# Power_Distribution_-_Spares_8-9_5V.net
KiCad netlist of a schematic drawn in Altium Designer
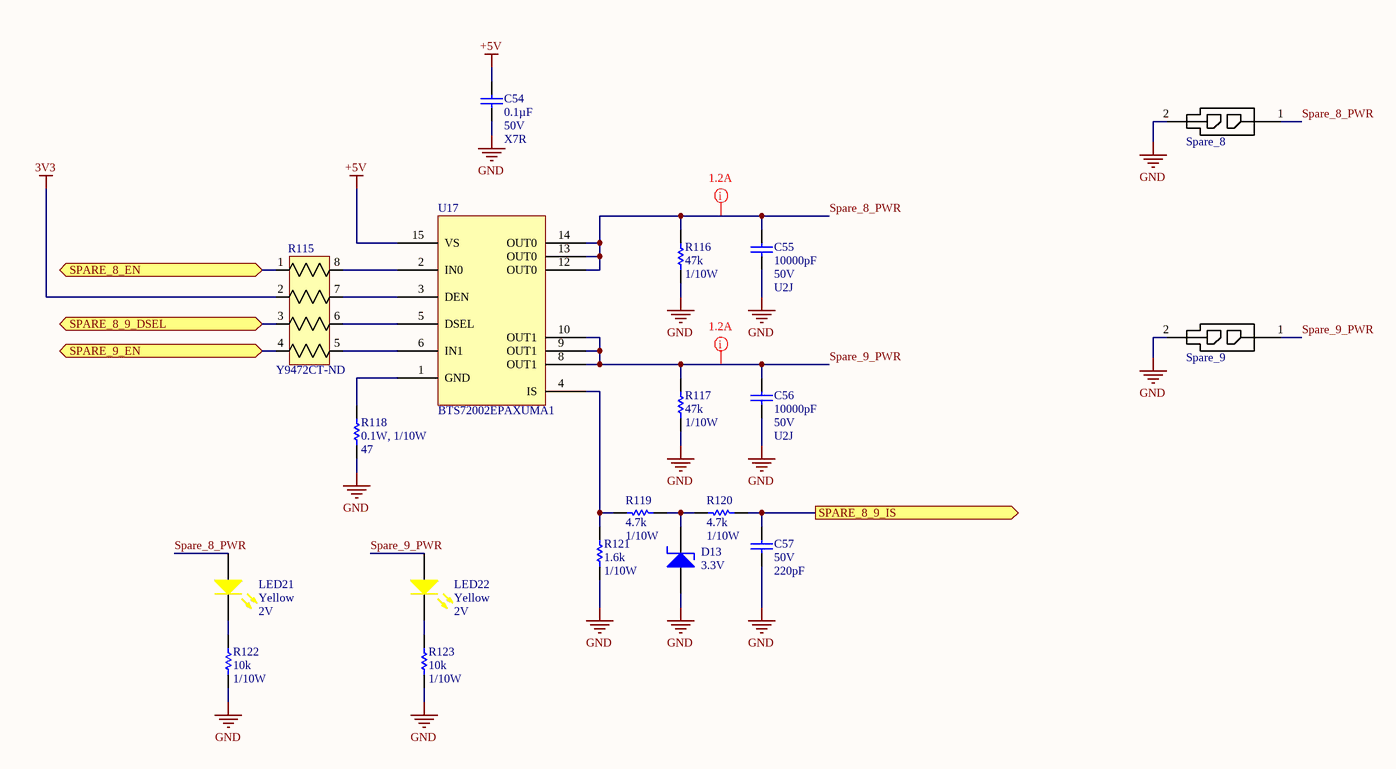
[diagram p0: Power Distribution - Spares 8-9 5V.SchDoc]

(export (version "E")
  (design (tool "Eeschema 10.0.6"))
  (components
    (comp (ref "C54")
      (value "CAP CER 0.1UF 50V 10% X7R 0603")
      (footprint "CAP, 0603")
      (description "0.10µF ±10% 50V Ceramic Capacitor X7R 0603 (1608 Metric)")
      (fields
        (field (name "TOLERANCE") "±10%")
        (field (name "CAPACITANCE") "0.1µF")
        (field (name "VOLTAGE") "50V")
        (field (name "TEMPERATURE COEFFICIENT") "X7R")
      )
      (libsource (lib "Schematic Diagrams") (part "CAP CER 0.1UF 50V 10% X7R 0603"))
    )
    (comp (ref "C55")
      (value "CAP CER 10nF 50V 5% X7R 0603")
      (footprint "CAP, 0603")
      (description "10000pF ±5% 50V Ceramic Capacitor U2J 0603 (1608 Metric)")
      (fields
        (field (name "TOLERANCE") "±5%")
        (field (name "CAPACITANCE") "10000pF")
        (field (name "VOLTAGE") "50V")
        (field (name "TEMPERATURE COEFFICIENT") "U2J")
      )
      (libsource (lib "Schematic Diagrams") (part "CAP CER 10nF 50V 5% X7R 0603"))
    )
    (comp (ref "C56")
      (value "CAP CER 10nF 50V 5% X7R 0603")
      (footprint "CAP, 0603")
      (description "10000pF ±5% 50V Ceramic Capacitor U2J 0603 (1608 Metric)")
      (fields
        (field (name "TOLERANCE") "±5%")
        (field (name "CAPACITANCE") "10000pF")
        (field (name "VOLTAGE") "50V")
        (field (name "TEMPERATURE COEFFICIENT") "U2J")
      )
      (libsource (lib "Schematic Diagrams") (part "CAP CER 10nF 50V 5% X7R 0603"))
    )
    (comp (ref "C57")
      (value "CAP CER 220PF 50V C0G/NP0 0603")
      (footprint "CAP, 0603")
      (description "220pF ±5% 50V Ceramic Capacitor C0G, NP0 0603 (1608 Metric)")
      (fields
        (field (name "MANUFACTURER") "KEMET")
        (field (name "TOLERANCE") "5%")
        (field (name "VOLTAGE RATING") "50V")
        (field (name "CAPACITANCE") "220pF")
      )
      (libsource (lib "Schematic Diagrams") (part "CAP CER 220PF 50V C0G/NP0 0603"))
    )
    (comp (ref "D13")
      (value "DIODE ZENER 3.3V 200MW SOD323")
      (footprint "sod-323")
      (description "Zener Diode 3.3V 200mW ±5% Surface Mount SOD-323")
      (fields (field (name "VOLTAGE") "3.3V"))
      (libsource (lib "Schematic Diagrams") (part "DIODE ZENER 3.3V 200MW SOD323"))
    )
    (comp (ref "LED21")
      (value "LED YELLOW CLEAR 2.1V 0603")
      (footprint "LED_0603")
      (description "Yellow 590nm LED Indication - Discrete 2V 0603 (1608 Metric)")
      (fields
        (field (name "MANUFACTURER") "Wurth Electronics Inc.")
        (field (name "MANUFACTURER PART NUMBER") "150060YS75000")
        (field (name "COLOR") "Yellow")
        (field (name "VOLTAGE - FORWARD (VF) (TYP)") "2V")
      )
      (libsource (lib "Schematic Diagrams") (part "LED YELLOW CLEAR 2.1V 0603"))
    )
    (comp (ref "LED22")
      (value "LED YELLOW CLEAR 2.1V 0603")
      (footprint "LED_0603")
      (description "Yellow 590nm LED Indication - Discrete 2V 0603 (1608 Metric)")
      (fields
        (field (name "MANUFACTURER") "Wurth Electronics Inc.")
        (field (name "MANUFACTURER PART NUMBER") "150060YS75000")
        (field (name "COLOR") "Yellow")
        (field (name "VOLTAGE - FORWARD (VF) (TYP)") "2V")
      )
      (libsource (lib "Schematic Diagrams") (part "LED YELLOW CLEAR 2.1V 0603"))
    )
    (comp (ref "R115")
      (value "RES ARRAY 4 RES 4.7K OHM 1206")
      (footprint "RES ARRAY 4RES 1206")
      (fields (field (name "TOLERANCE") "±5%") (field (name "SUPPLIER PART NUMBER 1") "Y9472CT-ND"))
      (libsource (lib "Schematic Diagrams") (part "RES ARRAY 4 RES 4.7K OHM 1206"))
    )
    (comp (ref "R116")
      (value "RES 47K OHM 1% 1/10W 0603")
      (footprint "RES, 0603")
      (description "47 kOhms ±1% 0.1W, 1/10W Chip Resistor 0603 (1608 Metric) Automotive AEC-Q200 Thick Film")
      (fields
        (field (name "MANUFACTURER") "Panasonic")
        (field (name "MANUFACTURER PART NUMBER") "ERJ3EKF4702V")
        (field (name "RESISTANCE") "47k")
        (field (name "POWER RATING") "1/10W")
      )
      (libsource (lib "Schematic Diagrams") (part "RES 47K OHM 1% 1/10W 0603"))
    )
    (comp (ref "R117")
      (value "RES 47K OHM 1% 1/10W 0603")
      (footprint "RES, 0603")
      (description "47 kOhms ±1% 0.1W, 1/10W Chip Resistor 0603 (1608 Metric) Automotive AEC-Q200 Thick Film")
      (fields
        (field (name "MANUFACTURER") "Panasonic")
        (field (name "MANUFACTURER PART NUMBER") "ERJ3EKF4702V")
        (field (name "RESISTANCE") "47k")
        (field (name "POWER RATING") "1/10W")
      )
      (libsource (lib "Schematic Diagrams") (part "RES 47K OHM 1% 1/10W 0603"))
    )
    (comp (ref "R118")
      (value "RES SMD 47 OHM 1% 1/10W 0603")
      (footprint "RES, 0603")
      (fields
        (field (name "TOLERANCE") "±1%")
        (field (name "POWER (WATTS)") "0.1W, 1/10W")
        (field (name "VALUES") "47")
      )
      (libsource (lib "Schematic Diagrams") (part "RES SMD 47 OHM 1% 1/10W 0603"))
    )
    (comp (ref "R119")
      (value "RES 4.7K OHM 1% 1/10W 0603")
      (footprint "RES, 0603")
      (description "4.7k Ohm ±1% 0.1W, 1/10W Chip Resistor 0603 (1608 Metric) Moisture Resistant Thick Film")
      (fields
        (field (name "TOLERANCE") "±1%")
        (field (name "RESISTANCE (OHMS)") "4.7k")
        (field (name "POWER (WATTS)") "1/10W")
      )
      (libsource (lib "Schematic Diagrams") (part "RES 4.7K OHM 1% 1/10W 0603"))
    )
    (comp (ref "R120")
      (value "RES 4.7K OHM 1% 1/10W 0603")
      (footprint "RES, 0603")
      (description "4.7k Ohm ±1% 0.1W, 1/10W Chip Resistor 0603 (1608 Metric) Moisture Resistant Thick Film")
      (fields
        (field (name "TOLERANCE") "±1%")
        (field (name "RESISTANCE (OHMS)") "4.7k")
        (field (name "POWER (WATTS)") "1/10W")
      )
      (libsource (lib "Schematic Diagrams") (part "RES 4.7K OHM 1% 1/10W 0603"))
    )
    (comp (ref "R121")
      (value "RES 1.6K OHM 1% 1/10W 0603")
      (footprint "RES, 0603")
      (description "1.6 kOhms ±1% 0.1W, 1/10W Chip Resistor 0603 (1608 Metric) Moisture Resistant Thick Film")
      (fields
        (field (name "MANUFACTURER") "Yageo")
        (field (name "MANUFACTURER PART NUMBER") "RC0603FR-071K6L")
        (field (name "RESISTANCE") "1.6k")
        (field (name "POWER RATING") "1/10W")
      )
      (libsource (lib "Schematic Diagrams") (part "RES 1.6K OHM 1% 1/10W 0603"))
    )
    (comp (ref "R122")
      (value "RES 10K OHM 1% 1/10W 0603")
      (footprint "RES, 0603")
      (description "RES SMD 10K OHM 1% 1/10W 0603")
      (fields
        (field (name "TOLERANCE") "±1%")
        (field (name "RESISTANCE") "10k")
        (field (name "POWER") "1/10W")
      )
      (libsource (lib "Schematic Diagrams") (part "RES 10K OHM 1% 1/10W 0603"))
    )
    (comp (ref "R123")
      (value "RES 10K OHM 1% 1/10W 0603")
      (footprint "RES, 0603")
      (description "RES SMD 10K OHM 1% 1/10W 0603")
      (fields
        (field (name "TOLERANCE") "±1%")
        (field (name "RESISTANCE") "10k")
        (field (name "POWER") "1/10W")
      )
      (libsource (lib "Schematic Diagrams") (part "RES 10K OHM 1% 1/10W 0603"))
    )
    (comp (ref "Spare_8")
      (value "CONN 2POS MICRO-FIT 3mm")
      (footprint "CONN, 2POS MICRO-FIT")
      (description "Connector Header Through Hole 2 position")
      (fields (field (name "MANUFACTURER") "Molex") (field (name "MANUFACTURER PART NUMBER") "43045-0227"))
      (libsource (lib "Schematic Diagrams") (part "CONN 2POS MICRO-FIT 3mm"))
    )
    (comp (ref "Spare_9")
      (value "CONN 2POS MICRO-FIT 3mm")
      (footprint "CONN, 2POS MICRO-FIT")
      (description "Connector Header Through Hole 2 position")
      (fields (field (name "MANUFACTURER") "Molex") (field (name "MANUFACTURER PART NUMBER") "43045-0227"))
      (libsource (lib "Schematic Diagrams") (part "CONN 2POS MICRO-FIT 3mm"))
    )
    (comp (ref "U17")
      (value "IC LOAD SWITCH BTS7200-2EPA PG-TSDSO-14_1")
      (footprint "IC LOAD SWITCH PG-TSDSO-14-22")
      (description "Power Switch/Driver 1:1 N-Channel 1.2A PG-TSDSO-14-22")
      (fields
        (field (name "MANUFACTURER") "Infineon")
        (field (name "MANUFACTURER PART NUMBER") "BTS72002EPAXUMA1")
      )
      (libsource (lib "Schematic Diagrams") (part "IC LOAD SWITCH BTS7200-2EPA PG-TSDSO-14_1"))
    )
  )
  (nets
    (net (code "1") (name "+5V") (class "Default")
      (node (ref "C54") (pin "1") (pinfunction "1_1") (pintype "passive"))
      (node (ref "U17") (pin "15") (pinfunction "VS_15") (pintype "passive"))
    )
    (net (code "2") (name "/SPARE_8_9_DSEL") (class "Default")
      (node (ref "R115") (pin "3") (pinfunction "3_3") (pintype "passive"))
    )
    (net (code "3") (name "/SPARE_8_9_IS") (class "Default")
      (node (ref "C57") (pin "1") (pinfunction "1_1") (pintype "passive"))
      (node (ref "R120") (pin "1") (pinfunction "1_1") (pintype "passive"))
    )
    (net (code "4") (name "/SPARE_8_EN") (class "Default")
      (node (ref "R115") (pin "1") (pinfunction "1_1") (pintype "passive"))
    )
    (net (code "5") (name "/SPARE_9_EN") (class "Default")
      (node (ref "R115") (pin "4") (pinfunction "4_4") (pintype "passive"))
    )
    (net (code "6") (name "/Spare_8_PWR") (class "Default")
      (node (ref "C55") (pin "1") (pinfunction "1_1") (pintype "passive"))
      (node (ref "LED21") (pin "1") (pinfunction "A_1") (pintype "passive"))
      (node (ref "R116") (pin "1") (pinfunction "1_1") (pintype "passive"))
      (node (ref "Spare_8") (pin "1") (pinfunction "1_1") (pintype "passive"))
      (node (ref "U17") (pin "12") (pinfunction "OUT0_12") (pintype "passive"))
      (node (ref "U17") (pin "13") (pinfunction "OUT0_13") (pintype "passive"))
      (node (ref "U17") (pin "14") (pinfunction "OUT0_14") (pintype "passive"))
    )
    (net (code "7") (name "/Spare_9_PWR") (class "Default")
      (node (ref "C56") (pin "1") (pinfunction "1_1") (pintype "passive"))
      (node (ref "LED22") (pin "1") (pinfunction "A_1") (pintype "passive"))
      (node (ref "R117") (pin "1") (pinfunction "1_1") (pintype "passive"))
      (node (ref "Spare_9") (pin "1") (pinfunction "1_1") (pintype "passive"))
      (node (ref "U17") (pin "10") (pinfunction "OUT1_10") (pintype "passive"))
      (node (ref "U17") (pin "8") (pinfunction "OUT1_8") (pintype "passive"))
      (node (ref "U17") (pin "9") (pinfunction "OUT1_9") (pintype "passive"))
    )
    (net (code "8") (name "3V3") (class "Default")
      (node (ref "R115") (pin "2") (pinfunction "2_2") (pintype "passive"))
    )
    (net (code "9") (name "GND") (class "Default")
      (node (ref "C54") (pin "2") (pinfunction "2_2") (pintype "passive"))
      (node (ref "C55") (pin "2") (pinfunction "2_2") (pintype "passive"))
      (node (ref "C56") (pin "2") (pinfunction "2_2") (pintype "passive"))
      (node (ref "C57") (pin "2") (pinfunction "2_2") (pintype "passive"))
      (node (ref "D13") (pin "1") (pinfunction "A_1") (pintype "passive"))
      (node (ref "R116") (pin "2") (pinfunction "2_2") (pintype "passive"))
      (node (ref "R117") (pin "2") (pinfunction "2_2") (pintype "passive"))
      (node (ref "R118") (pin "2") (pinfunction "2_2") (pintype "passive"))
      (node (ref "R121") (pin "2") (pinfunction "2_2") (pintype "passive"))
      (node (ref "R122") (pin "2") (pinfunction "2_2") (pintype "passive"))
      (node (ref "R123") (pin "2") (pinfunction "2_2") (pintype "passive"))
      (node (ref "Spare_8") (pin "2") (pinfunction "2_2") (pintype "passive"))
      (node (ref "Spare_9") (pin "2") (pinfunction "2_2") (pintype "passive"))
    )
    (net (code "10") (name "Net-(D13-K)") (class "Default")
      (node (ref "D13") (pin "2") (pinfunction "K_2") (pintype "passive"))
      (node (ref "R119") (pin "1") (pinfunction "1_1") (pintype "passive"))
      (node (ref "R120") (pin "2") (pinfunction "2_2") (pintype "passive"))
    )
    (net (code "11") (name "Net-(LED21-K)") (class "Default")
      (node (ref "LED21") (pin "2") (pinfunction "K_2") (pintype "passive"))
      (node (ref "R122") (pin "1") (pinfunction "1_1") (pintype "passive"))
    )
    (net (code "12") (name "Net-(LED22-K)") (class "Default")
      (node (ref "LED22") (pin "2") (pinfunction "K_2") (pintype "passive"))
      (node (ref "R123") (pin "1") (pinfunction "1_1") (pintype "passive"))
    )
    (net (code "13") (name "Net-(U17-DEN)") (class "Default")
      (node (ref "R115") (pin "7") (pinfunction "7_7") (pintype "passive"))
      (node (ref "U17") (pin "3") (pinfunction "DEN_3") (pintype "passive"))
    )
    (net (code "14") (name "Net-(U17-DSEL)") (class "Default")
      (node (ref "R115") (pin "6") (pinfunction "6_6") (pintype "passive"))
      (node (ref "U17") (pin "5") (pinfunction "DSEL_5") (pintype "passive"))
    )
    (net (code "15") (name "Net-(U17-GND)") (class "Default")
      (node (ref "R118") (pin "1") (pinfunction "1_1") (pintype "passive"))
      (node (ref "U17") (pin "1") (pinfunction "GND_1") (pintype "passive"))
    )
    (net (code "16") (name "Net-(U17-IN0)") (class "Default")
      (node (ref "R115") (pin "8") (pinfunction "8_8") (pintype "passive"))
      (node (ref "U17") (pin "2") (pinfunction "IN0_2") (pintype "passive"))
    )
    (net (code "17") (name "Net-(U17-IN1)") (class "Default")
      (node (ref "R115") (pin "5") (pinfunction "5_5") (pintype "passive"))
      (node (ref "U17") (pin "6") (pinfunction "IN1_6") (pintype "passive"))
    )
    (net (code "18") (name "Net-(U17-IS)") (class "Default")
      (node (ref "R119") (pin "2") (pinfunction "2_2") (pintype "passive"))
      (node (ref "R121") (pin "1") (pinfunction "1_1") (pintype "passive"))
      (node (ref "U17") (pin "4") (pinfunction "IS_4") (pintype "passive"))
    )
  )
)
